# lit-pic1.net
KiCad netlist of a schematic drawn in EAGLE
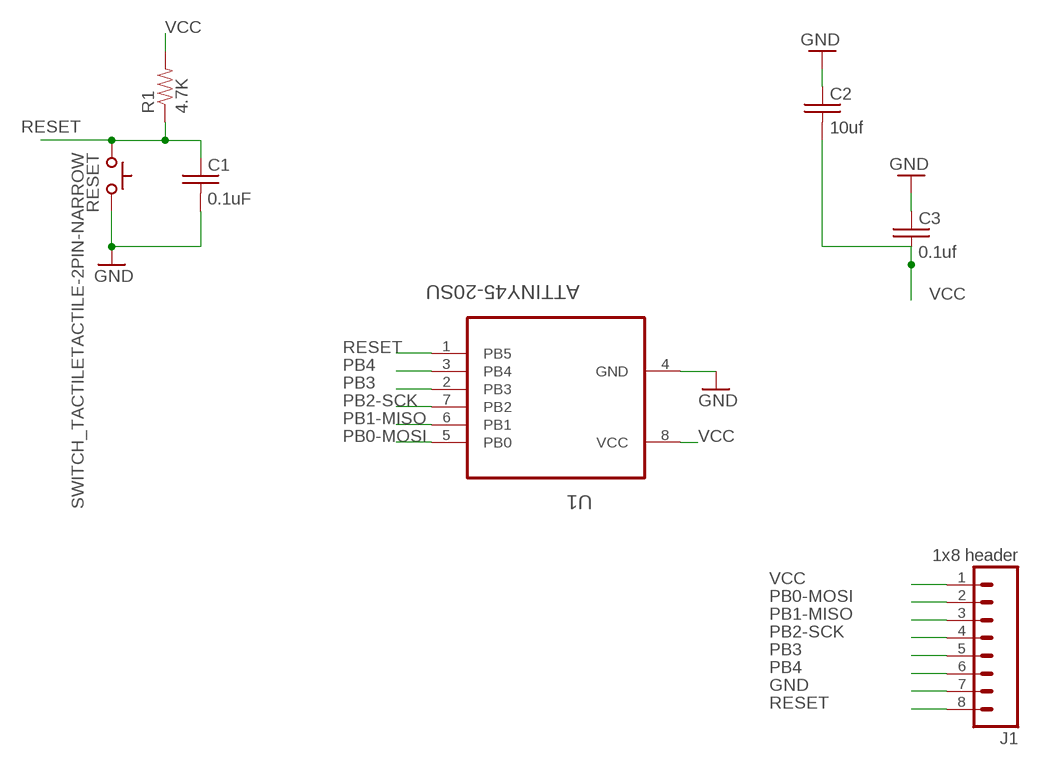
[diagram p0: schematic, sheet 1]
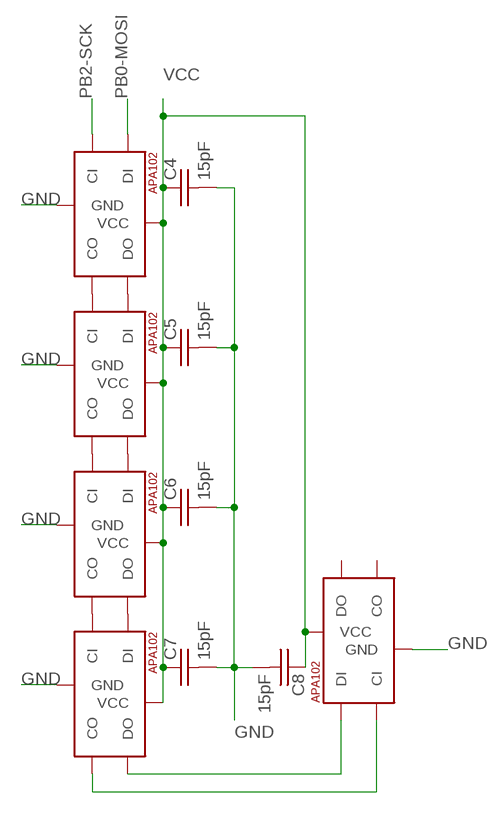
[diagram p1: schematic, sheet 2]

(export (version "E")
  (design (tool "Eeschema 10.0.6"))
  (components
    (comp (ref "C4")
      (value "15pF")
      (footprint "eagle-import:C0805K")
      (libsource (lib "eagle-import") (part "passives_C-USC0805K"))
    )
    (comp (ref "C5")
      (value "15pF")
      (footprint "eagle-import:C0805K")
      (libsource (lib "eagle-import") (part "passives_C-USC0805K"))
    )
    (comp (ref "C6")
      (value "15pF")
      (footprint "eagle-import:C0805K")
      (libsource (lib "eagle-import") (part "passives_C-USC0805K"))
    )
    (comp (ref "C7")
      (value "15pF")
      (footprint "eagle-import:C0805K")
      (libsource (lib "eagle-import") (part "passives_C-USC0805K"))
    )
    (comp (ref "C8")
      (value "15pF")
      (footprint "eagle-import:C0805K")
      (libsource (lib "eagle-import") (part "passives_C-USC0805K"))
    )
    (comp (ref "U$1")
      (value "APA1025050")
      (footprint "eagle-import:APA102_5050")
      (libsource (lib "eagle-import") (part "APA1025050"))
    )
    (comp (ref "U$2")
      (value "APA1025050")
      (footprint "eagle-import:APA102_5050")
      (libsource (lib "eagle-import") (part "APA1025050"))
    )
    (comp (ref "U$3")
      (value "APA1025050")
      (footprint "eagle-import:APA102_5050")
      (libsource (lib "eagle-import") (part "APA1025050"))
    )
    (comp (ref "U$4")
      (value "APA1025050")
      (footprint "eagle-import:APA102_5050")
      (libsource (lib "eagle-import") (part "APA1025050"))
    )
    (comp (ref "U$5")
      (value "APA1025050")
      (footprint "eagle-import:APA102_5050")
      (libsource (lib "eagle-import") (part "APA1025050"))
    )
    (comp (ref "C1")
      (value "0.1uF")
      (footprint "eagle-import:C0805K")
      (libsource (lib "eagle-import") (part "C-USC0805K"))
    )
    (comp (ref "C2")
      (value "10uf")
      (footprint "eagle-import:C0805K")
      (libsource (lib "eagle-import") (part "C-USC0805K"))
    )
    (comp (ref "C3")
      (value "0.1uf")
      (footprint "eagle-import:C0805K")
      (libsource (lib "eagle-import") (part "C-USC0805K"))
    )
    (comp (ref "J1")
      (value "1x8 header")
      (footprint "eagle-import:1X08")
      (libsource (lib "eagle-import") (part "M08SILK_FEMALE_PTH"))
    )
    (comp (ref "R1")
      (value "4.7K")
      (footprint "eagle-import:R0805")
      (libsource (lib "eagle-import") (part "RESISTORR0805-RES"))
    )
    (comp (ref "RESET")
      (value "SWITCH_TACTILETACTILE-2PIN-NARROW")
      (footprint "eagle-import:TACTILE-2PIN-NARROW")
      (libsource (lib "eagle-import") (part "SWITCH_TACTILETACTILE-2PIN-NARROW"))
    )
    (comp (ref "U1")
      (value "ATTINY45-20SU")
      (footprint "eagle-import:SOIC127P798X216-8N")
      (fields (field (name "DIGI-KEY_PART_NUMBER") "ATTINY45-20SU-ND") (field (name "MF") "Microchip"))
      (libsource (lib "eagle-import") (part "ATTINY45-20SU"))
    )
  )
  (nets
    (net (code "1") (name "GND") (class "Default")
      (node (ref "C1") (pin "2") (pinfunction "2_2") (pintype "passive"))
      (node (ref "C2") (pin "1") (pinfunction "1_1") (pintype "passive"))
      (node (ref "C3") (pin "1") (pinfunction "1_1") (pintype "passive"))
      (node (ref "C4") (pin "2") (pinfunction "2_2") (pintype "passive"))
      (node (ref "C5") (pin "2") (pinfunction "2_2") (pintype "passive"))
      (node (ref "C6") (pin "2") (pinfunction "2_2") (pintype "passive"))
      (node (ref "C7") (pin "2") (pinfunction "2_2") (pintype "passive"))
      (node (ref "C8") (pin "2") (pinfunction "2_2") (pintype "passive"))
      (node (ref "J1") (pin "7") (pinfunction "7_7") (pintype "passive"))
      (node (ref "RESET") (pin "P$1") (pinfunction "A_P$1") (pintype "passive"))
      (node (ref "U$1") (pin "6") (pinfunction "GND_6") (pintype "bidirectional"))
      (node (ref "U$2") (pin "6") (pinfunction "GND_6") (pintype "bidirectional"))
      (node (ref "U$3") (pin "6") (pinfunction "GND_6") (pintype "bidirectional"))
      (node (ref "U$4") (pin "6") (pinfunction "GND_6") (pintype "bidirectional"))
      (node (ref "U$5") (pin "6") (pinfunction "GND_6") (pintype "bidirectional"))
      (node (ref "U1") (pin "4") (pinfunction "GND_4") (pintype "passive"))
    )
    (net (code "2") (name "Net-(U$1-CO)") (class "Default")
      (node (ref "U$1") (pin "2") (pinfunction "CO_2") (pintype "bidirectional"))
      (node (ref "U$2") (pin "5") (pinfunction "CI_5") (pintype "bidirectional"))
    )
    (net (code "3") (name "Net-(U$1-DO)") (class "Default")
      (node (ref "U$1") (pin "3") (pinfunction "DO_3") (pintype "bidirectional"))
      (node (ref "U$2") (pin "4") (pinfunction "DI_4") (pintype "bidirectional"))
    )
    (net (code "4") (name "Net-(U$2-CO)") (class "Default")
      (node (ref "U$2") (pin "2") (pinfunction "CO_2") (pintype "bidirectional"))
      (node (ref "U$3") (pin "5") (pinfunction "CI_5") (pintype "bidirectional"))
    )
    (net (code "5") (name "Net-(U$2-DO)") (class "Default")
      (node (ref "U$2") (pin "3") (pinfunction "DO_3") (pintype "bidirectional"))
      (node (ref "U$3") (pin "4") (pinfunction "DI_4") (pintype "bidirectional"))
    )
    (net (code "6") (name "Net-(U$3-CO)") (class "Default")
      (node (ref "U$3") (pin "2") (pinfunction "CO_2") (pintype "bidirectional"))
      (node (ref "U$4") (pin "5") (pinfunction "CI_5") (pintype "bidirectional"))
    )
    (net (code "7") (name "Net-(U$3-DO)") (class "Default")
      (node (ref "U$3") (pin "3") (pinfunction "DO_3") (pintype "bidirectional"))
      (node (ref "U$4") (pin "4") (pinfunction "DI_4") (pintype "bidirectional"))
    )
    (net (code "8") (name "Net-(U$4-CO)") (class "Default")
      (node (ref "U$4") (pin "2") (pinfunction "CO_2") (pintype "bidirectional"))
      (node (ref "U$5") (pin "5") (pinfunction "CI_5") (pintype "bidirectional"))
    )
    (net (code "9") (name "Net-(U$4-DO)") (class "Default")
      (node (ref "U$4") (pin "3") (pinfunction "DO_3") (pintype "bidirectional"))
      (node (ref "U$5") (pin "4") (pinfunction "DI_4") (pintype "bidirectional"))
    )
    (net (code "10") (name "PB0-MOSI") (class "Default")
      (node (ref "J1") (pin "2") (pinfunction "2_2") (pintype "passive"))
      (node (ref "U$1") (pin "4") (pinfunction "DI_4") (pintype "bidirectional"))
      (node (ref "U1") (pin "5") (pinfunction "PB0_5") (pintype "bidirectional"))
    )
    (net (code "11") (name "PB1-MISO") (class "Default")
      (node (ref "J1") (pin "3") (pinfunction "3_3") (pintype "passive"))
      (node (ref "U1") (pin "6") (pinfunction "PB1_6") (pintype "bidirectional"))
    )
    (net (code "12") (name "PB2-SCK") (class "Default")
      (node (ref "J1") (pin "4") (pinfunction "4_4") (pintype "passive"))
      (node (ref "U$1") (pin "5") (pinfunction "CI_5") (pintype "bidirectional"))
      (node (ref "U1") (pin "7") (pinfunction "PB2_7") (pintype "bidirectional"))
    )
    (net (code "13") (name "PB3") (class "Default")
      (node (ref "J1") (pin "5") (pinfunction "5_5") (pintype "passive"))
      (node (ref "U1") (pin "2") (pinfunction "PB3_2") (pintype "bidirectional"))
    )
    (net (code "14") (name "PB4") (class "Default")
      (node (ref "J1") (pin "6") (pinfunction "6_6") (pintype "passive"))
      (node (ref "U1") (pin "3") (pinfunction "PB4_3") (pintype "bidirectional"))
    )
    (net (code "15") (name "RESET") (class "Default")
      (node (ref "C1") (pin "1") (pinfunction "1_1") (pintype "passive"))
      (node (ref "J1") (pin "8") (pinfunction "8_8") (pintype "passive"))
      (node (ref "R1") (pin "1") (pinfunction "1_1") (pintype "passive"))
      (node (ref "RESET") (pin "P$2") (pinfunction "C_P$2") (pintype "passive"))
      (node (ref "U1") (pin "1") (pinfunction "PB5_1") (pintype "bidirectional"))
    )
    (net (code "16") (name "VCC") (class "Default")
      (node (ref "C2") (pin "2") (pinfunction "2_2") (pintype "passive"))
      (node (ref "C3") (pin "2") (pinfunction "2_2") (pintype "passive"))
      (node (ref "C4") (pin "1") (pinfunction "1_1") (pintype "passive"))
      (node (ref "C5") (pin "1") (pinfunction "1_1") (pintype "passive"))
      (node (ref "C6") (pin "1") (pinfunction "1_1") (pintype "passive"))
      (node (ref "C7") (pin "1") (pinfunction "1_1") (pintype "passive"))
      (node (ref "C8") (pin "1") (pinfunction "1_1") (pintype "passive"))
      (node (ref "J1") (pin "1") (pinfunction "1_1") (pintype "passive"))
      (node (ref "R1") (pin "2") (pinfunction "2_2") (pintype "passive"))
      (node (ref "U$1") (pin "1") (pinfunction "VCC_1") (pintype "bidirectional"))
      (node (ref "U$2") (pin "1") (pinfunction "VCC_1") (pintype "bidirectional"))
      (node (ref "U$3") (pin "1") (pinfunction "VCC_1") (pintype "bidirectional"))
      (node (ref "U$4") (pin "1") (pinfunction "VCC_1") (pintype "bidirectional"))
      (node (ref "U$5") (pin "1") (pinfunction "VCC_1") (pintype "bidirectional"))
      (node (ref "U1") (pin "8") (pinfunction "VCC_8") (pintype "power_in"))
    )
    (net (code "17") (name "unconnected-(U$5-CO-Pad2)") (class "Default")
      (node (ref "U$5") (pin "2") (pinfunction "CO_2") (pintype "bidirectional"))
    )
    (net (code "18") (name "unconnected-(U$5-DO-Pad3)") (class "Default")
      (node (ref "U$5") (pin "3") (pinfunction "DO_3") (pintype "bidirectional"))
    )
  )
)
